# STK-681-332-E_EvalBoard_OwnRoutingStarte.net
KiCad netlist of a schematic drawn in EAGLE
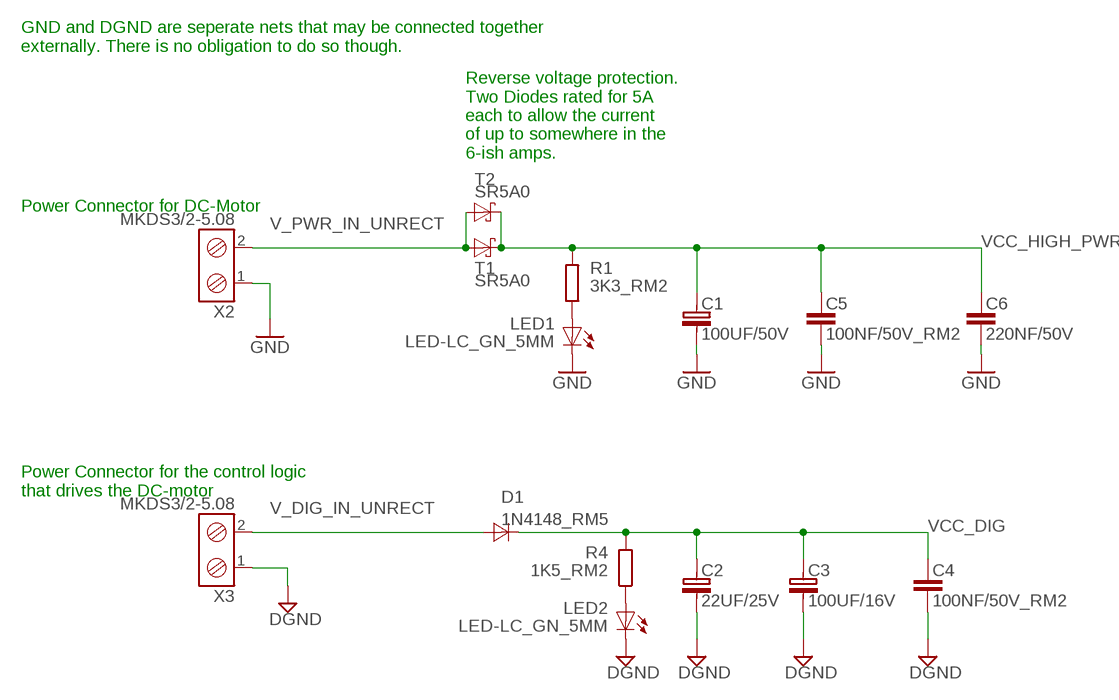
[diagram p0: schematic, sheet 1]
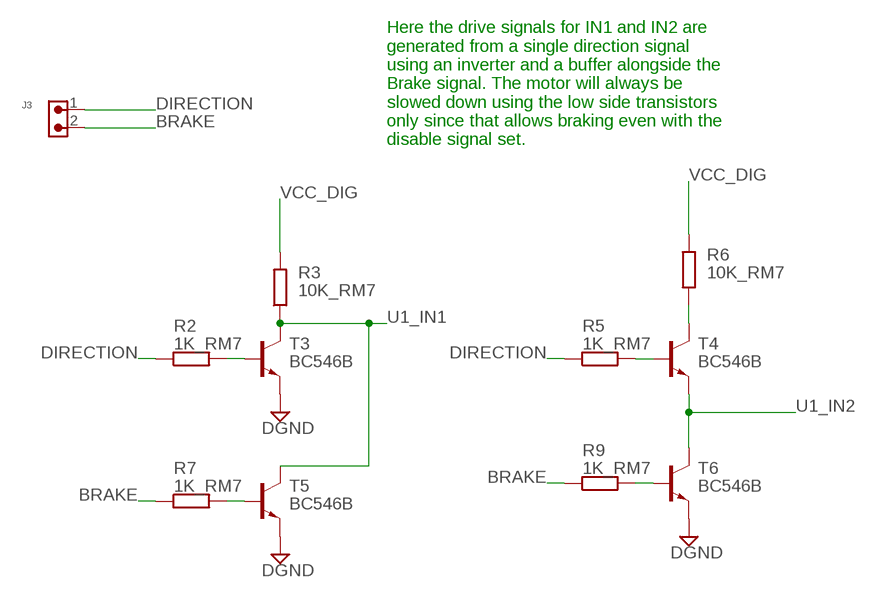
[diagram p1: schematic, sheet 2]
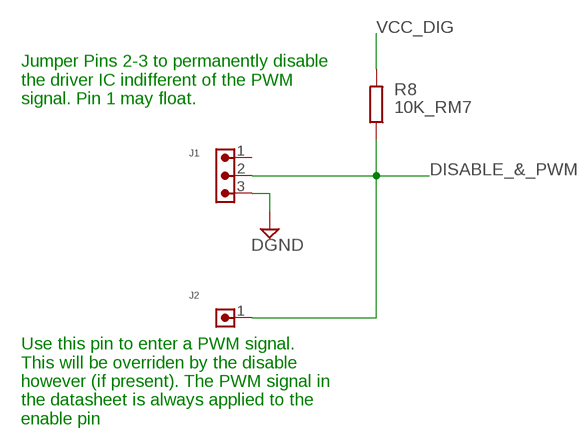
[diagram p2: schematic, sheet 3]
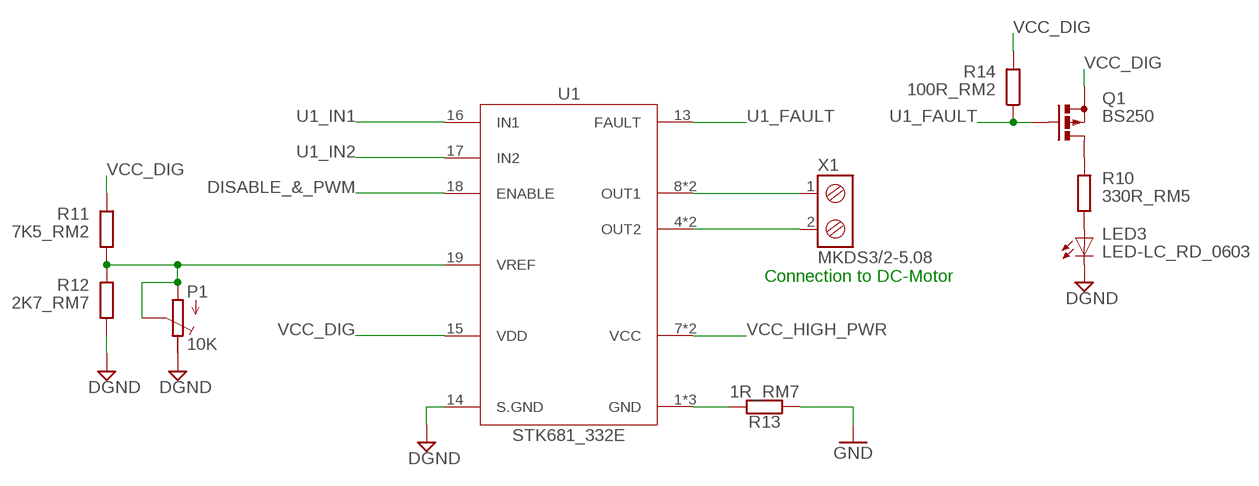
[diagram p3: schematic, sheet 4]

(export (version "E")
  (design (tool "Eeschema 10.0.6"))
  (components
    (comp (ref "C1")
      (value "100UF/50V")
      (footprint "eagle-import:RM3,5D8")
      (libsource (lib "eagle-import") (part "100UF/50V"))
    )
    (comp (ref "C2")
      (value "22UF/25V")
      (footprint "eagle-import:RM2D5")
      (libsource (lib "eagle-import") (part "22UF/25V"))
    )
    (comp (ref "C3")
      (value "100UF/16V")
      (footprint "eagle-import:RM2,5D6")
      (libsource (lib "eagle-import") (part "100UF/16V"))
    )
    (comp (ref "C4")
      (value "100NF/50V_RM2")
      (footprint "eagle-import:RM2.54")
      (libsource (lib "eagle-import") (part "100NF/50V_RM2"))
    )
    (comp (ref "C5")
      (value "100NF/50V_RM2")
      (footprint "eagle-import:RM2.54")
      (libsource (lib "eagle-import") (part "100NF/50V_RM2"))
    )
    (comp (ref "C6")
      (value "220NF/50V")
      (footprint "eagle-import:RM2.54")
      (libsource (lib "eagle-import") (part "220NF/50V"))
    )
    (comp (ref "D1")
      (value "1N4148_RM5")
      (footprint "eagle-import:DO35_RM5.08")
      (libsource (lib "eagle-import") (part "1N4148_RM5"))
    )
    (comp (ref "LED1")
      (value "LED-LC_GN_5MM")
      (footprint "eagle-import:LED5MM")
      (libsource (lib "eagle-import") (part "LED-LC_GN_5MM"))
    )
    (comp (ref "LED2")
      (value "LED-LC_GN_5MM")
      (footprint "eagle-import:LED5MM")
      (libsource (lib "eagle-import") (part "LED-LC_GN_5MM"))
    )
    (comp (ref "R1")
      (value "3K3_RM2")
      (footprint "eagle-import:RM2.54")
      (libsource (lib "eagle-import") (part "3K3_RM2"))
    )
    (comp (ref "R4")
      (value "1K5_RM2")
      (footprint "eagle-import:RM2.54")
      (libsource (lib "eagle-import") (part "1K5_RM2"))
    )
    (comp (ref "T1")
      (value "SR5A0")
      (footprint "eagle-import:DO201_RM10.16")
      (libsource (lib "eagle-import") (part "SR5A0"))
    )
    (comp (ref "T2")
      (value "SR5A0")
      (footprint "eagle-import:DO201_RM10.16")
      (libsource (lib "eagle-import") (part "SR5A0"))
    )
    (comp (ref "X2")
      (value "MKDS3/2-5.08")
      (footprint "eagle-import:MKDS3_2-5.08")
      (libsource (lib "eagle-import") (part "MKDS3/2-5.08"))
    )
    (comp (ref "X3")
      (value "MKDS3/2-5.08")
      (footprint "eagle-import:MKDS3_2-5.08")
      (libsource (lib "eagle-import") (part "MKDS3/2-5.08"))
    )
    (comp (ref "J3")
      (value "6130XX11121_61300211121")
      (footprint "eagle-import:61300211121")
      (libsource (lib "eagle-import") (part "6130XX11121_61300211121"))
    )
    (comp (ref "R2")
      (value "1K_RM7")
      (footprint "eagle-import:RM7.62")
      (libsource (lib "eagle-import") (part "1K_RM7"))
    )
    (comp (ref "R3")
      (value "10K_RM7")
      (footprint "eagle-import:RM7.62")
      (libsource (lib "eagle-import") (part "10K_RM7"))
    )
    (comp (ref "R5")
      (value "1K_RM7")
      (footprint "eagle-import:RM7.62")
      (libsource (lib "eagle-import") (part "1K_RM7"))
    )
    (comp (ref "R6")
      (value "10K_RM7")
      (footprint "eagle-import:RM7.62")
      (libsource (lib "eagle-import") (part "10K_RM7"))
    )
    (comp (ref "R7")
      (value "1K_RM7")
      (footprint "eagle-import:RM7.62")
      (libsource (lib "eagle-import") (part "1K_RM7"))
    )
    (comp (ref "R9")
      (value "1K_RM7")
      (footprint "eagle-import:RM7.62")
      (libsource (lib "eagle-import") (part "1K_RM7"))
    )
    (comp (ref "T3")
      (value "BC546B")
      (footprint "eagle-import:TO92")
      (libsource (lib "eagle-import") (part "BC546B"))
    )
    (comp (ref "T4")
      (value "BC546B")
      (footprint "eagle-import:TO92")
      (libsource (lib "eagle-import") (part "BC546B"))
    )
    (comp (ref "T5")
      (value "BC546B")
      (footprint "eagle-import:TO92")
      (libsource (lib "eagle-import") (part "BC546B"))
    )
    (comp (ref "T6")
      (value "BC546B")
      (footprint "eagle-import:TO92")
      (libsource (lib "eagle-import") (part "BC546B"))
    )
    (comp (ref "J1")
      (value "6130XX11121_61300311121")
      (footprint "eagle-import:61300311121")
      (libsource (lib "eagle-import") (part "6130XX11121_61300311121"))
    )
    (comp (ref "J2")
      (value "6130XX11121_61300111121")
      (footprint "eagle-import:61300111121")
      (libsource (lib "eagle-import") (part "6130XX11121_61300111121"))
    )
    (comp (ref "R8")
      (value "10K_RM7")
      (footprint "eagle-import:RM7.62")
      (libsource (lib "eagle-import") (part "10K_RM7"))
    )
    (comp (ref "LED3")
      (value "LED-LC_RD_0603")
      (footprint "eagle-import:0603")
      (libsource (lib "eagle-import") (part "LED-LC_RD_0603"))
    )
    (comp (ref "P1")
      (value "10K")
      (footprint "eagle-import:R_TRIMM")
      (libsource (lib "eagle-import") (part "10K"))
    )
    (comp (ref "Q1")
      (value "BS250")
      (footprint "eagle-import:SOT54E")
      (libsource (lib "eagle-import") (part "BS250"))
    )
    (comp (ref "R10")
      (value "330R_RM5")
      (footprint "eagle-import:RM5.08")
      (libsource (lib "eagle-import") (part "330R_RM5"))
    )
    (comp (ref "R11")
      (value "7K5_RM2")
      (footprint "eagle-import:RM2.54")
      (libsource (lib "eagle-import") (part "7K5_RM2"))
    )
    (comp (ref "R12")
      (value "2K7_RM7")
      (footprint "eagle-import:RM7.62")
      (libsource (lib "eagle-import") (part "2K7_RM7"))
    )
    (comp (ref "R13")
      (value "1R_RM7")
      (footprint "eagle-import:RM7.62")
      (libsource (lib "eagle-import") (part "1R_RM7"))
    )
    (comp (ref "R14")
      (value "100R_RM2")
      (footprint "eagle-import:RM2.54")
      (libsource (lib "eagle-import") (part "100R_RM2"))
    )
    (comp (ref "U1")
      (value "STK681_332E")
      (footprint "eagle-import:SIP19")
      (libsource (lib "eagle-import") (part "STK681_332E"))
    )
    (comp (ref "X1")
      (value "MKDS3/2-5.08")
      (footprint "eagle-import:MKDS3_2-5.08")
      (libsource (lib "eagle-import") (part "MKDS3/2-5.08"))
    )
  )
  (nets
    (net (code "1") (name "BRAKE") (class "Default")
      (node (ref "J3") (pin "2") (pinfunction "2_2") (pintype "passive"))
      (node (ref "R7") (pin "1") (pinfunction "1_1") (pintype "passive"))
      (node (ref "R9") (pin "1") (pinfunction "1_1") (pintype "passive"))
    )
    (net (code "2") (name "DGND") (class "Default")
      (node (ref "C2") (pin "-") (pinfunction "-_-") (pintype "passive"))
      (node (ref "C3") (pin "-") (pinfunction "-_-") (pintype "passive"))
      (node (ref "C4") (pin "2") (pinfunction "2_2") (pintype "passive"))
      (node (ref "J1") (pin "3") (pinfunction "3_3") (pintype "passive"))
      (node (ref "LED2") (pin "K") (pinfunction "C_K") (pintype "passive"))
      (node (ref "LED3") (pin "K") (pinfunction "C_K") (pintype "passive"))
      (node (ref "P1") (pin "3") (pinfunction "E_3") (pintype "passive"))
      (node (ref "R12") (pin "1") (pinfunction "1_1") (pintype "passive"))
      (node (ref "T3") (pin "3") (pinfunction "E_3") (pintype "passive"))
      (node (ref "T5") (pin "3") (pinfunction "E_3") (pintype "passive"))
      (node (ref "T6") (pin "3") (pinfunction "E_3") (pintype "passive"))
      (node (ref "U1") (pin "14") (pinfunction "S.GND_14") (pintype "power_in"))
      (node (ref "X3") (pin "1") (pinfunction "1_1") (pintype "passive"))
    )
    (net (code "3") (name "DIRECTION") (class "Default")
      (node (ref "J3") (pin "1") (pinfunction "1_1") (pintype "passive"))
      (node (ref "R2") (pin "1") (pinfunction "1_1") (pintype "passive"))
      (node (ref "R5") (pin "1") (pinfunction "1_1") (pintype "passive"))
    )
    (net (code "4") (name "DISABLE_&_PWM") (class "Default")
      (node (ref "J1") (pin "2") (pinfunction "2_2") (pintype "passive"))
      (node (ref "J2") (pin "1") (pinfunction "1_1") (pintype "passive"))
      (node (ref "R8") (pin "1") (pinfunction "1_1") (pintype "passive"))
      (node (ref "U1") (pin "18") (pinfunction "ENABLE_18") (pintype "input"))
    )
    (net (code "5") (name "GND") (class "Default")
      (node (ref "C1") (pin "-") (pinfunction "-_-") (pintype "passive"))
      (node (ref "C5") (pin "2") (pinfunction "2_2") (pintype "passive"))
      (node (ref "C6") (pin "2") (pinfunction "2_2") (pintype "passive"))
      (node (ref "LED1") (pin "K") (pinfunction "C_K") (pintype "passive"))
      (node (ref "R13") (pin "1") (pinfunction "1_1") (pintype "passive"))
      (node (ref "X2") (pin "1") (pinfunction "1_1") (pintype "passive"))
    )
    (net (code "6") (name "Net-(LED1-PadA)") (class "Default")
      (node (ref "LED1") (pin "A") (pinfunction "A_A") (pintype "passive"))
      (node (ref "R1") (pin "1") (pinfunction "1_1") (pintype "passive"))
    )
    (net (code "7") (name "Net-(LED2-PadA)") (class "Default")
      (node (ref "LED2") (pin "A") (pinfunction "A_A") (pintype "passive"))
      (node (ref "R4") (pin "1") (pinfunction "1_1") (pintype "passive"))
    )
    (net (code "8") (name "Net-(LED3-PadA)") (class "Default")
      (node (ref "LED3") (pin "A") (pinfunction "A_A") (pintype "passive"))
      (node (ref "R10") (pin "1") (pinfunction "1_1") (pintype "passive"))
    )
    (net (code "9") (name "Net-(P1-A)") (class "Default")
      (node (ref "P1") (pin "1") (pinfunction "A_1") (pintype "passive"))
      (node (ref "P1") (pin "2") (pinfunction "S_2") (pintype "passive"))
      (node (ref "R11") (pin "1") (pinfunction "1_1") (pintype "passive"))
      (node (ref "R12") (pin "2") (pinfunction "2_2") (pintype "passive"))
      (node (ref "U1") (pin "19") (pinfunction "VREF_19") (pintype "power_in"))
    )
    (net (code "10") (name "Net-(Q1-PadD)") (class "Default")
      (node (ref "Q1") (pin "D") (pinfunction "D_D") (pintype "passive"))
      (node (ref "R10") (pin "2") (pinfunction "2_2") (pintype "passive"))
    )
    (net (code "11") (name "Net-(R13-Pad2)") (class "Default")
      (node (ref "R13") (pin "2") (pinfunction "2_2") (pintype "passive"))
      (node (ref "U1") (pin "1") (pinfunction "GND_1") (pintype "power_in"))
      (node (ref "U1") (pin "2") (pinfunction "GND_2") (pintype "power_in"))
      (node (ref "U1") (pin "3") (pinfunction "GND_3") (pintype "power_in"))
    )
    (net (code "12") (name "Net-(T3-B)") (class "Default")
      (node (ref "R2") (pin "2") (pinfunction "2_2") (pintype "passive"))
      (node (ref "T3") (pin "2") (pinfunction "B_2") (pintype "passive"))
    )
    (net (code "13") (name "Net-(T4-B)") (class "Default")
      (node (ref "R5") (pin "2") (pinfunction "2_2") (pintype "passive"))
      (node (ref "T4") (pin "2") (pinfunction "B_2") (pintype "passive"))
    )
    (net (code "14") (name "Net-(T4-C)") (class "Default")
      (node (ref "R6") (pin "1") (pinfunction "1_1") (pintype "passive"))
      (node (ref "T4") (pin "1") (pinfunction "C_1") (pintype "passive"))
    )
    (net (code "15") (name "Net-(T5-B)") (class "Default")
      (node (ref "R7") (pin "2") (pinfunction "2_2") (pintype "passive"))
      (node (ref "T5") (pin "2") (pinfunction "B_2") (pintype "passive"))
    )
    (net (code "16") (name "Net-(T6-B)") (class "Default")
      (node (ref "R9") (pin "2") (pinfunction "2_2") (pintype "passive"))
      (node (ref "T6") (pin "2") (pinfunction "B_2") (pintype "passive"))
    )
    (net (code "17") (name "Net-(U1-OUT1-Pad10)") (class "Default")
      (node (ref "U1") (pin "10") (pinfunction "OUT1_10") (pintype "output"))
      (node (ref "U1") (pin "8") (pinfunction "OUT1_8") (pintype "output"))
      (node (ref "X1") (pin "1") (pinfunction "1_1") (pintype "passive"))
    )
    (net (code "18") (name "Net-(U1-OUT2-Pad4)") (class "Default")
      (node (ref "U1") (pin "4") (pinfunction "OUT2_4") (pintype "output"))
      (node (ref "U1") (pin "6") (pinfunction "OUT2_6") (pintype "output"))
      (node (ref "X1") (pin "2") (pinfunction "2_2") (pintype "passive"))
    )
    (net (code "19") (name "U1_FAULT") (class "Default")
      (node (ref "Q1") (pin "G") (pinfunction "G_G") (pintype "passive"))
      (node (ref "R14") (pin "1") (pinfunction "1_1") (pintype "passive"))
      (node (ref "U1") (pin "13") (pinfunction "FAULT_13") (pintype "output"))
    )
    (net (code "20") (name "U1_IN1") (class "Default")
      (node (ref "R3") (pin "1") (pinfunction "1_1") (pintype "passive"))
      (node (ref "T3") (pin "1") (pinfunction "C_1") (pintype "passive"))
      (node (ref "T5") (pin "1") (pinfunction "C_1") (pintype "passive"))
      (node (ref "U1") (pin "16") (pinfunction "IN1_16") (pintype "input"))
    )
    (net (code "21") (name "U1_IN2") (class "Default")
      (node (ref "T4") (pin "3") (pinfunction "E_3") (pintype "passive"))
      (node (ref "T6") (pin "1") (pinfunction "C_1") (pintype "passive"))
      (node (ref "U1") (pin "17") (pinfunction "IN2_17") (pintype "input"))
    )
    (net (code "22") (name "VCC_DIG") (class "Default")
      (node (ref "C2") (pin "+") (pinfunction "+_+") (pintype "passive"))
      (node (ref "C3") (pin "+") (pinfunction "+_+") (pintype "passive"))
      (node (ref "C4") (pin "1") (pinfunction "1_1") (pintype "passive"))
      (node (ref "D1") (pin "K") (pinfunction "K_K") (pintype "passive"))
      (node (ref "Q1") (pin "S") (pinfunction "S_S") (pintype "passive"))
      (node (ref "R11") (pin "2") (pinfunction "2_2") (pintype "passive"))
      (node (ref "R14") (pin "2") (pinfunction "2_2") (pintype "passive"))
      (node (ref "R3") (pin "2") (pinfunction "2_2") (pintype "passive"))
      (node (ref "R4") (pin "2") (pinfunction "2_2") (pintype "passive"))
      (node (ref "R6") (pin "2") (pinfunction "2_2") (pintype "passive"))
      (node (ref "R8") (pin "2") (pinfunction "2_2") (pintype "passive"))
      (node (ref "U1") (pin "15") (pinfunction "VDD_15") (pintype "power_in"))
    )
    (net (code "23") (name "VCC_HIGH_PWR") (class "Default")
      (node (ref "C1") (pin "+") (pinfunction "+_+") (pintype "passive"))
      (node (ref "C5") (pin "1") (pinfunction "1_1") (pintype "passive"))
      (node (ref "C6") (pin "1") (pinfunction "1_1") (pintype "passive"))
      (node (ref "R1") (pin "2") (pinfunction "2_2") (pintype "passive"))
      (node (ref "T1") (pin "K") (pinfunction "K_K") (pintype "passive"))
      (node (ref "T2") (pin "K") (pinfunction "K_K") (pintype "passive"))
      (node (ref "U1") (pin "7") (pinfunction "VCC_7") (pintype "power_in"))
      (node (ref "U1") (pin "9") (pinfunction "VCC_9") (pintype "power_in"))
    )
    (net (code "24") (name "V_DIG_IN_UNRECT") (class "Default")
      (node (ref "D1") (pin "A") (pinfunction "A_A") (pintype "passive"))
      (node (ref "X3") (pin "2") (pinfunction "2_2") (pintype "passive"))
    )
    (net (code "25") (name "V_PWR_IN_UNRECT") (class "Default")
      (node (ref "T1") (pin "A") (pinfunction "A_A") (pintype "passive"))
      (node (ref "T2") (pin "A") (pinfunction "A_A") (pintype "passive"))
      (node (ref "X2") (pin "2") (pinfunction "2_2") (pintype "passive"))
    )
    (net (code "26") (name "unconnected-(J1-Pad1)") (class "Default")
      (node (ref "J1") (pin "1") (pinfunction "1_1") (pintype "passive"))
    )
    (net (code "27") (name "unconnected-(U1-NC-Pad5)") (class "Default")
      (node (ref "U1") (pin "5") (pinfunction "NC_5") (pintype "no_connect"))
    )
    (net (code "28") (name "unconnected-(U1-NC-Pad11)") (class "Default")
      (node (ref "U1") (pin "11") (pinfunction "NC_11") (pintype "no_connect"))
    )
    (net (code "29") (name "unconnected-(U1-NC-Pad12)") (class "Default")
      (node (ref "U1") (pin "12") (pinfunction "NC_12") (pintype "no_connect"))
    )
  )
)
